# gcplus2_0.net
KiCad netlist of a schematic drawn in EAGLE
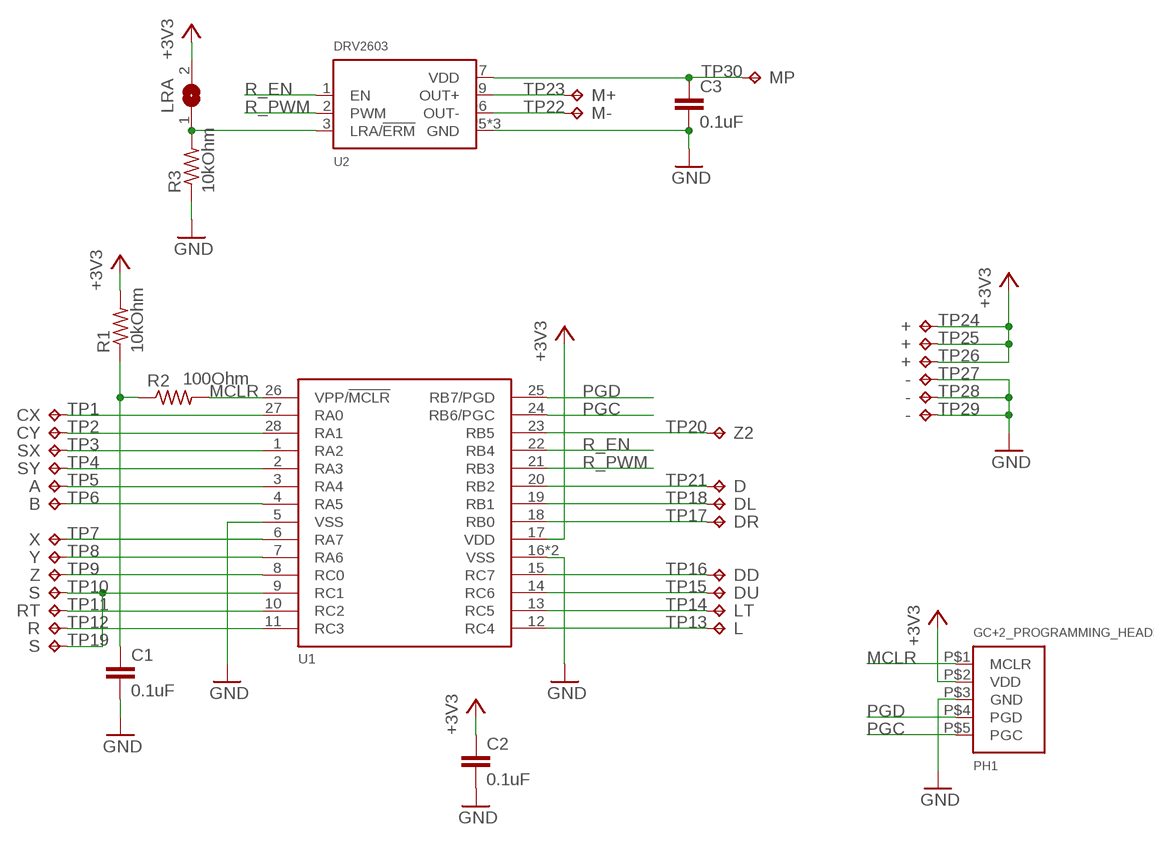
[diagram p0: schematic, sheet 1]

(export (version "E")
  (design (tool "Eeschema 10.0.6"))
  (components
    (comp (ref "C1")
      (value "0.1uF")
      (footprint "eagle-import:C0402")
      (libsource (lib "eagle-import") (part "C-EUC0402"))
    )
    (comp (ref "C2")
      (value "0.1uF")
      (footprint "eagle-import:C0402")
      (libsource (lib "eagle-import") (part "C-EUC0402"))
    )
    (comp (ref "C3")
      (value "0.1uF")
      (footprint "eagle-import:C0402")
      (libsource (lib "eagle-import") (part "C-EUC0402"))
    )
    (comp (ref "LRA") (value "SJ") (footprint "eagle-import:SJ") (libsource (lib "eagle-import") (part "SJ")))
    (comp (ref "PH1")
      (value "GC+2_PROGRAMMING_HEADER")
      (footprint "eagle-import:GC+2_PROGRAMMING_HEADER")
      (libsource (lib "eagle-import") (part "GC+2_PROGRAMMING_HEADER"))
    )
    (comp (ref "R1")
      (value "10kOhm")
      (footprint "eagle-import:R0402")
      (libsource (lib "eagle-import") (part "R-US_R0402"))
    )
    (comp (ref "R2")
      (value "100Ohm")
      (footprint "eagle-import:R0402")
      (libsource (lib "eagle-import") (part "R-US_R0402"))
    )
    (comp (ref "R3")
      (value "10kOhm")
      (footprint "eagle-import:R0402")
      (libsource (lib "eagle-import") (part "R-US_R0402"))
    )
    (comp (ref "TP1")
      (value "TPTP10SQ")
      (footprint "eagle-import:TP10SQ")
      (fields (field (name "TP_SIGNAL_NAME") "CX"))
      (libsource (lib "eagle-import") (part "TPTP10SQ"))
    )
    (comp (ref "TP2")
      (value "TPTP10SQ")
      (footprint "eagle-import:TP10SQ")
      (fields (field (name "TP_SIGNAL_NAME") "CY"))
      (libsource (lib "eagle-import") (part "TPTP10SQ"))
    )
    (comp (ref "TP3")
      (value "TPTP10SQ")
      (footprint "eagle-import:TP10SQ")
      (fields (field (name "TP_SIGNAL_NAME") "SX"))
      (libsource (lib "eagle-import") (part "TPTP10SQ"))
    )
    (comp (ref "TP4")
      (value "TPTP10SQ")
      (footprint "eagle-import:TP10SQ")
      (fields (field (name "TP_SIGNAL_NAME") "SY"))
      (libsource (lib "eagle-import") (part "TPTP10SQ"))
    )
    (comp (ref "TP5")
      (value "TPTP10SQ")
      (footprint "eagle-import:TP10SQ")
      (fields (field (name "TP_SIGNAL_NAME") "A"))
      (libsource (lib "eagle-import") (part "TPTP10SQ"))
    )
    (comp (ref "TP6")
      (value "TPTP10SQ")
      (footprint "eagle-import:TP10SQ")
      (fields (field (name "TP_SIGNAL_NAME") "B"))
      (libsource (lib "eagle-import") (part "TPTP10SQ"))
    )
    (comp (ref "TP7")
      (value "TPTP10SQ")
      (footprint "eagle-import:TP10SQ")
      (fields (field (name "TP_SIGNAL_NAME") "X"))
      (libsource (lib "eagle-import") (part "TPTP10SQ"))
    )
    (comp (ref "TP8")
      (value "TPTP10SQ")
      (footprint "eagle-import:TP10SQ")
      (fields (field (name "TP_SIGNAL_NAME") "Y"))
      (libsource (lib "eagle-import") (part "TPTP10SQ"))
    )
    (comp (ref "TP9")
      (value "TPTP10SQ")
      (footprint "eagle-import:TP10SQ")
      (fields (field (name "TP_SIGNAL_NAME") "Z"))
      (libsource (lib "eagle-import") (part "TPTP10SQ"))
    )
    (comp (ref "TP10")
      (value "TPTP10SQ")
      (footprint "eagle-import:TP10SQ")
      (fields (field (name "TP_SIGNAL_NAME") "S"))
      (libsource (lib "eagle-import") (part "TPTP10SQ"))
    )
    (comp (ref "TP11")
      (value "TPTP10SQ")
      (footprint "eagle-import:TP10SQ")
      (fields (field (name "TP_SIGNAL_NAME") "RT"))
      (libsource (lib "eagle-import") (part "TPTP10SQ"))
    )
    (comp (ref "TP12")
      (value "TPTP10SQ")
      (footprint "eagle-import:TP10SQ")
      (fields (field (name "TP_SIGNAL_NAME") "R"))
      (libsource (lib "eagle-import") (part "TPTP10SQ"))
    )
    (comp (ref "TP13")
      (value "TPTP10SQ")
      (footprint "eagle-import:TP10SQ")
      (fields (field (name "TP_SIGNAL_NAME") "L"))
      (libsource (lib "eagle-import") (part "TPTP10SQ"))
    )
    (comp (ref "TP14")
      (value "TPTP10SQ")
      (footprint "eagle-import:TP10SQ")
      (fields (field (name "TP_SIGNAL_NAME") "LT"))
      (libsource (lib "eagle-import") (part "TPTP10SQ"))
    )
    (comp (ref "TP15")
      (value "TPTP10SQ")
      (footprint "eagle-import:TP10SQ")
      (fields (field (name "TP_SIGNAL_NAME") "DU"))
      (libsource (lib "eagle-import") (part "TPTP10SQ"))
    )
    (comp (ref "TP16")
      (value "TPTP10SQ")
      (footprint "eagle-import:TP10SQ")
      (fields (field (name "TP_SIGNAL_NAME") "DD"))
      (libsource (lib "eagle-import") (part "TPTP10SQ"))
    )
    (comp (ref "TP17")
      (value "TPTP10SQ")
      (footprint "eagle-import:TP10SQ")
      (fields (field (name "TP_SIGNAL_NAME") "DR"))
      (libsource (lib "eagle-import") (part "TPTP10SQ"))
    )
    (comp (ref "TP18")
      (value "TPTP10SQ")
      (footprint "eagle-import:TP10SQ")
      (fields (field (name "TP_SIGNAL_NAME") "DL"))
      (libsource (lib "eagle-import") (part "TPTP10SQ"))
    )
    (comp (ref "TP19")
      (value "TPTP10SQ")
      (footprint "eagle-import:TP10SQ")
      (fields (field (name "TP_SIGNAL_NAME") "S"))
      (libsource (lib "eagle-import") (part "TPTP10SQ"))
    )
    (comp (ref "TP20")
      (value "TPTP10SQ")
      (footprint "eagle-import:TP10SQ")
      (fields (field (name "TP_SIGNAL_NAME") "Z2"))
      (libsource (lib "eagle-import") (part "TPTP10SQ"))
    )
    (comp (ref "TP21")
      (value "TPTP10SQ")
      (footprint "eagle-import:TP10SQ")
      (fields (field (name "TP_SIGNAL_NAME") "D"))
      (libsource (lib "eagle-import") (part "TPTP10SQ"))
    )
    (comp (ref "TP22")
      (value "TPTP10SQ")
      (footprint "eagle-import:TP10SQ")
      (fields (field (name "TP_SIGNAL_NAME") "M-"))
      (libsource (lib "eagle-import") (part "TPTP10SQ"))
    )
    (comp (ref "TP23")
      (value "TPTP10SQ")
      (footprint "eagle-import:TP10SQ")
      (fields (field (name "TP_SIGNAL_NAME") "M+"))
      (libsource (lib "eagle-import") (part "TPTP10SQ"))
    )
    (comp (ref "TP24")
      (value "TPTP10SQ")
      (footprint "eagle-import:TP10SQ")
      (fields (field (name "TP_SIGNAL_NAME") "+"))
      (libsource (lib "eagle-import") (part "TPTP10SQ"))
    )
    (comp (ref "TP25")
      (value "TPTP10SQ")
      (footprint "eagle-import:TP10SQ")
      (fields (field (name "TP_SIGNAL_NAME") "+"))
      (libsource (lib "eagle-import") (part "TPTP10SQ"))
    )
    (comp (ref "TP26")
      (value "TPTP10SQ")
      (footprint "eagle-import:TP10SQ")
      (fields (field (name "TP_SIGNAL_NAME") "+"))
      (libsource (lib "eagle-import") (part "TPTP10SQ"))
    )
    (comp (ref "TP27")
      (value "TPTP10SQ")
      (footprint "eagle-import:TP10SQ")
      (fields (field (name "TP_SIGNAL_NAME") "-"))
      (libsource (lib "eagle-import") (part "TPTP10SQ"))
    )
    (comp (ref "TP28")
      (value "TPTP10SQ")
      (footprint "eagle-import:TP10SQ")
      (fields (field (name "TP_SIGNAL_NAME") "-"))
      (libsource (lib "eagle-import") (part "TPTP10SQ"))
    )
    (comp (ref "TP29")
      (value "TPTP10SQ")
      (footprint "eagle-import:TP10SQ")
      (fields (field (name "TP_SIGNAL_NAME") "-"))
      (libsource (lib "eagle-import") (part "TPTP10SQ"))
    )
    (comp (ref "TP30")
      (value "TPTP10SQ")
      (footprint "eagle-import:TP10SQ")
      (fields (field (name "TP_SIGNAL_NAME") "MP"))
      (libsource (lib "eagle-import") (part "TPTP10SQ"))
    )
    (comp (ref "U1")
      (value "PIC18F25K42")
      (footprint "eagle-import:QFN-28")
      (libsource (lib "eagle-import") (part "PIC18F25K42"))
    )
    (comp (ref "U2")
      (value "DRV2603")
      (footprint "eagle-import:WQFN-10")
      (libsource (lib "eagle-import") (part "DRV2603"))
    )
  )
  (nets
    (net (code "1") (name "+3V3") (class "Default")
      (node (ref "C2") (pin "1") (pinfunction "1_1") (pintype "passive"))
      (node (ref "LRA") (pin "2") (pinfunction "2_2") (pintype "passive"))
      (node (ref "PH1") (pin "P$2") (pinfunction "VDD_P$2") (pintype "bidirectional"))
      (node (ref "R1") (pin "2") (pinfunction "2_2") (pintype "passive"))
      (node (ref "TP24") (pin "TP") (pinfunction "TP_TP") (pintype "input"))
      (node (ref "TP25") (pin "TP") (pinfunction "TP_TP") (pintype "input"))
      (node (ref "TP26") (pin "TP") (pinfunction "TP_TP") (pintype "input"))
      (node (ref "U1") (pin "17") (pinfunction "VDD_17") (pintype "bidirectional"))
    )
    (net (code "2") (name "/MCLR") (class "Default")
      (node (ref "PH1") (pin "P$1") (pinfunction "MCLR_P$1") (pintype "bidirectional"))
      (node (ref "R2") (pin "2") (pinfunction "2_2") (pintype "passive"))
      (node (ref "U1") (pin "26") (pinfunction "VPP/~{MCLR}_26") (pintype "bidirectional"))
    )
    (net (code "3") (name "/PGC") (class "Default")
      (node (ref "PH1") (pin "P$5") (pinfunction "PGC_P$5") (pintype "bidirectional"))
      (node (ref "U1") (pin "24") (pinfunction "RB6/PGC_24") (pintype "bidirectional"))
    )
    (net (code "4") (name "/PGD") (class "Default")
      (node (ref "PH1") (pin "P$4") (pinfunction "PGD_P$4") (pintype "bidirectional"))
      (node (ref "U1") (pin "25") (pinfunction "RB7/PGD_25") (pintype "bidirectional"))
    )
    (net (code "5") (name "/R_EN") (class "Default")
      (node (ref "U1") (pin "22") (pinfunction "RB4_22") (pintype "bidirectional"))
      (node (ref "U2") (pin "1") (pinfunction "EN_1") (pintype "bidirectional"))
    )
    (net (code "6") (name "/R_PWM") (class "Default")
      (node (ref "U1") (pin "21") (pinfunction "RB3_21") (pintype "bidirectional"))
      (node (ref "U2") (pin "2") (pinfunction "PWM_2") (pintype "bidirectional"))
    )
    (net (code "7") (name "GND") (class "Default")
      (node (ref "C1") (pin "2") (pinfunction "2_2") (pintype "passive"))
      (node (ref "C2") (pin "2") (pinfunction "2_2") (pintype "passive"))
      (node (ref "C3") (pin "2") (pinfunction "2_2") (pintype "passive"))
      (node (ref "PH1") (pin "P$3") (pinfunction "GND_P$3") (pintype "bidirectional"))
      (node (ref "R3") (pin "1") (pinfunction "1_1") (pintype "passive"))
      (node (ref "TP27") (pin "TP") (pinfunction "TP_TP") (pintype "input"))
      (node (ref "TP28") (pin "TP") (pinfunction "TP_TP") (pintype "input"))
      (node (ref "TP29") (pin "TP") (pinfunction "TP_TP") (pintype "input"))
      (node (ref "U1") (pin "16") (pinfunction "VSS_16") (pintype "bidirectional"))
      (node (ref "U1") (pin "5") (pinfunction "VSS_5") (pintype "bidirectional"))
      (node (ref "U1") (pin "PAD") (pinfunction "VSS_PAD") (pintype "bidirectional"))
      (node (ref "U2") (pin "10") (pinfunction "GND_10") (pintype "bidirectional"))
      (node (ref "U2") (pin "5") (pinfunction "GND_5") (pintype "bidirectional"))
      (node (ref "U2") (pin "8") (pinfunction "GND_8") (pintype "bidirectional"))
    )
    (net (code "8") (name "Net-(C1-Pad1)") (class "Default")
      (node (ref "C1") (pin "1") (pinfunction "1_1") (pintype "passive"))
      (node (ref "R1") (pin "1") (pinfunction "1_1") (pintype "passive"))
      (node (ref "R2") (pin "1") (pinfunction "1_1") (pintype "passive"))
    )
    (net (code "9") (name "Net-(U1-RA0)") (class "Default")
      (node (ref "TP1") (pin "TP") (pinfunction "TP_TP") (pintype "input"))
      (node (ref "U1") (pin "27") (pinfunction "RA0_27") (pintype "bidirectional"))
    )
    (net (code "10") (name "Net-(U1-RA1)") (class "Default")
      (node (ref "TP2") (pin "TP") (pinfunction "TP_TP") (pintype "input"))
      (node (ref "U1") (pin "28") (pinfunction "RA1_28") (pintype "bidirectional"))
    )
    (net (code "11") (name "Net-(U1-RA2)") (class "Default")
      (node (ref "TP3") (pin "TP") (pinfunction "TP_TP") (pintype "input"))
      (node (ref "U1") (pin "1") (pinfunction "RA2_1") (pintype "bidirectional"))
    )
    (net (code "12") (name "Net-(U1-RA3)") (class "Default")
      (node (ref "TP4") (pin "TP") (pinfunction "TP_TP") (pintype "input"))
      (node (ref "U1") (pin "2") (pinfunction "RA3_2") (pintype "bidirectional"))
    )
    (net (code "13") (name "Net-(U1-RA4)") (class "Default")
      (node (ref "TP5") (pin "TP") (pinfunction "TP_TP") (pintype "input"))
      (node (ref "U1") (pin "3") (pinfunction "RA4_3") (pintype "bidirectional"))
    )
    (net (code "14") (name "Net-(U1-RA5)") (class "Default")
      (node (ref "TP6") (pin "TP") (pinfunction "TP_TP") (pintype "input"))
      (node (ref "U1") (pin "4") (pinfunction "RA5_4") (pintype "bidirectional"))
    )
    (net (code "15") (name "Net-(U1-RA6)") (class "Default")
      (node (ref "TP8") (pin "TP") (pinfunction "TP_TP") (pintype "input"))
      (node (ref "U1") (pin "7") (pinfunction "RA6_7") (pintype "bidirectional"))
    )
    (net (code "16") (name "Net-(U1-RA7)") (class "Default")
      (node (ref "TP7") (pin "TP") (pinfunction "TP_TP") (pintype "input"))
      (node (ref "U1") (pin "6") (pinfunction "RA7_6") (pintype "bidirectional"))
    )
    (net (code "17") (name "Net-(U1-RB0)") (class "Default")
      (node (ref "TP17") (pin "TP") (pinfunction "TP_TP") (pintype "input"))
      (node (ref "U1") (pin "18") (pinfunction "RB0_18") (pintype "bidirectional"))
    )
    (net (code "18") (name "Net-(U1-RB1)") (class "Default")
      (node (ref "TP18") (pin "TP") (pinfunction "TP_TP") (pintype "input"))
      (node (ref "U1") (pin "19") (pinfunction "RB1_19") (pintype "bidirectional"))
    )
    (net (code "19") (name "Net-(U1-RB2)") (class "Default")
      (node (ref "TP21") (pin "TP") (pinfunction "TP_TP") (pintype "input"))
      (node (ref "U1") (pin "20") (pinfunction "RB2_20") (pintype "bidirectional"))
    )
    (net (code "20") (name "Net-(U1-RB5)") (class "Default")
      (node (ref "TP20") (pin "TP") (pinfunction "TP_TP") (pintype "input"))
      (node (ref "U1") (pin "23") (pinfunction "RB5_23") (pintype "bidirectional"))
    )
    (net (code "21") (name "Net-(U1-RC0)") (class "Default")
      (node (ref "TP9") (pin "TP") (pinfunction "TP_TP") (pintype "input"))
      (node (ref "U1") (pin "8") (pinfunction "RC0_8") (pintype "bidirectional"))
    )
    (net (code "22") (name "Net-(U1-RC1)") (class "Default")
      (node (ref "TP10") (pin "TP") (pinfunction "TP_TP") (pintype "input"))
      (node (ref "TP19") (pin "TP") (pinfunction "TP_TP") (pintype "input"))
      (node (ref "U1") (pin "9") (pinfunction "RC1_9") (pintype "bidirectional"))
    )
    (net (code "23") (name "Net-(U1-RC2)") (class "Default")
      (node (ref "TP11") (pin "TP") (pinfunction "TP_TP") (pintype "input"))
      (node (ref "U1") (pin "10") (pinfunction "RC2_10") (pintype "bidirectional"))
    )
    (net (code "24") (name "Net-(U1-RC3)") (class "Default")
      (node (ref "TP12") (pin "TP") (pinfunction "TP_TP") (pintype "input"))
      (node (ref "U1") (pin "11") (pinfunction "RC3_11") (pintype "bidirectional"))
    )
    (net (code "25") (name "Net-(U1-RC4)") (class "Default")
      (node (ref "TP13") (pin "TP") (pinfunction "TP_TP") (pintype "input"))
      (node (ref "U1") (pin "12") (pinfunction "RC4_12") (pintype "bidirectional"))
    )
    (net (code "26") (name "Net-(U1-RC5)") (class "Default")
      (node (ref "TP14") (pin "TP") (pinfunction "TP_TP") (pintype "input"))
      (node (ref "U1") (pin "13") (pinfunction "RC5_13") (pintype "bidirectional"))
    )
    (net (code "27") (name "Net-(U1-RC6)") (class "Default")
      (node (ref "TP15") (pin "TP") (pinfunction "TP_TP") (pintype "input"))
      (node (ref "U1") (pin "14") (pinfunction "RC6_14") (pintype "bidirectional"))
    )
    (net (code "28") (name "Net-(U1-RC7)") (class "Default")
      (node (ref "TP16") (pin "TP") (pinfunction "TP_TP") (pintype "input"))
      (node (ref "U1") (pin "15") (pinfunction "RC7_15") (pintype "bidirectional"))
    )
    (net (code "29") (name "Net-(U2-LRA{slash}~{ERM})") (class "Default")
      (node (ref "LRA") (pin "1") (pinfunction "1_1") (pintype "passive"))
      (node (ref "R3") (pin "2") (pinfunction "2_2") (pintype "passive"))
      (node (ref "U2") (pin "3") (pinfunction "LRA/~{ERM}_3") (pintype "bidirectional"))
    )
    (net (code "30") (name "Net-(U2-OUT+)") (class "Default")
      (node (ref "TP23") (pin "TP") (pinfunction "TP_TP") (pintype "input"))
      (node (ref "U2") (pin "9") (pinfunction "OUT+_9") (pintype "bidirectional"))
    )
    (net (code "31") (name "Net-(U2-OUT-)") (class "Default")
      (node (ref "TP22") (pin "TP") (pinfunction "TP_TP") (pintype "input"))
      (node (ref "U2") (pin "6") (pinfunction "OUT-_6") (pintype "bidirectional"))
    )
    (net (code "32") (name "Net-(U2-VDD)") (class "Default")
      (node (ref "C3") (pin "1") (pinfunction "1_1") (pintype "passive"))
      (node (ref "TP30") (pin "TP") (pinfunction "TP_TP") (pintype "input"))
      (node (ref "U2") (pin "7") (pinfunction "VDD_7") (pintype "bidirectional"))
    )
  )
)
